# WSTL18P2_SHIELD.net
KiCad netlist of a schematic drawn in EAGLE
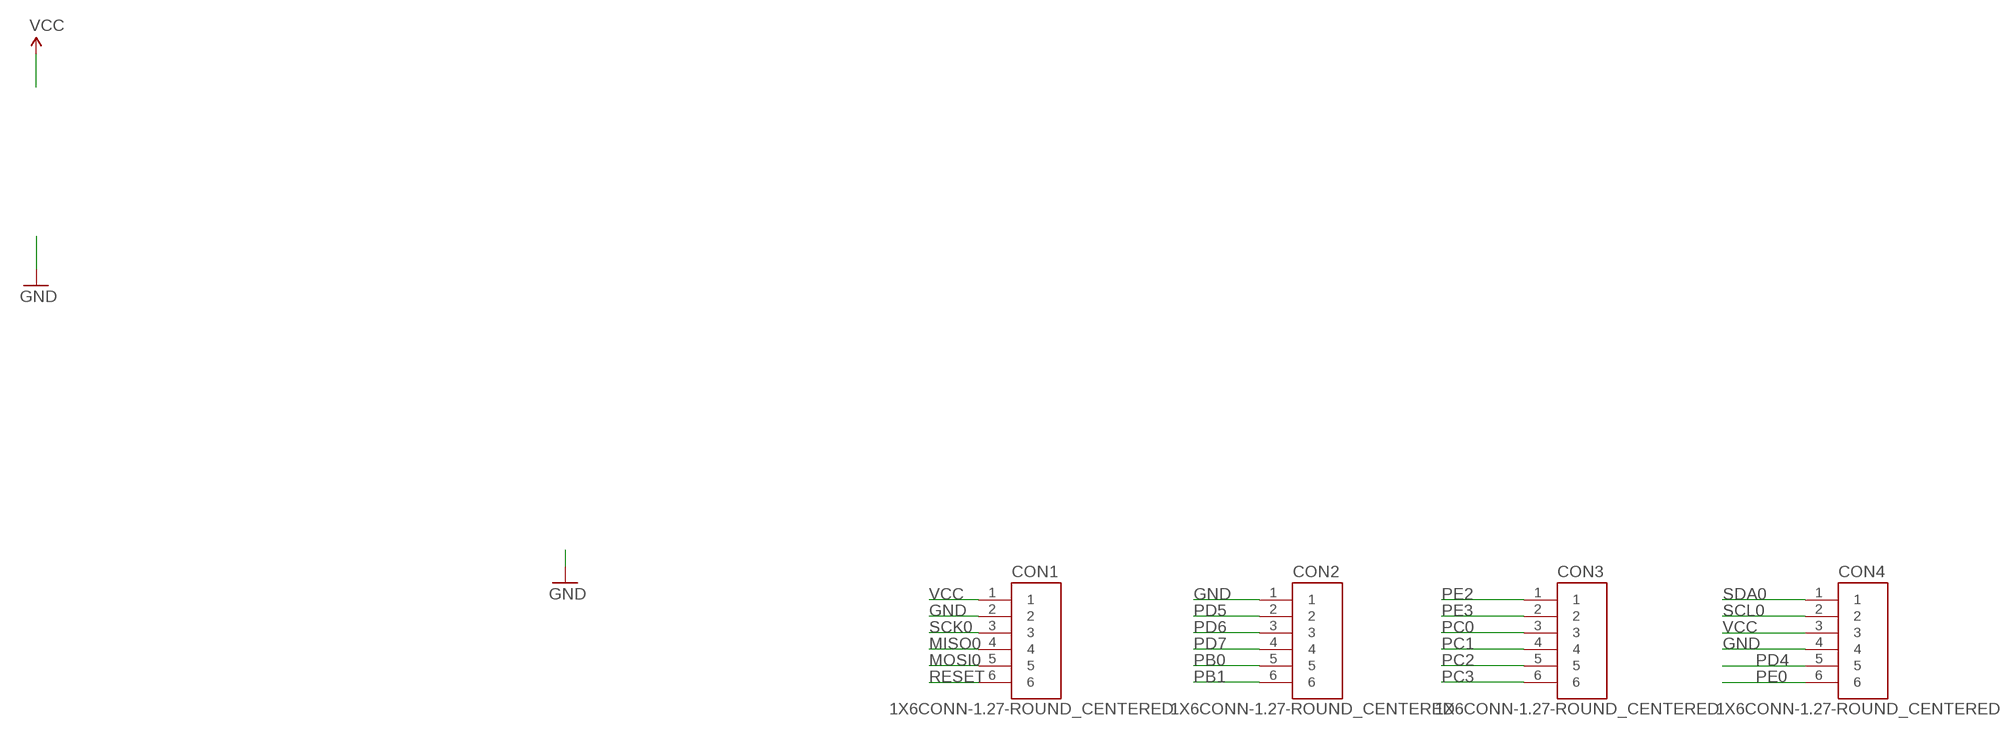
[diagram p0: schematic, sheet 1]

(export (version "E")
  (design (tool "Eeschema 10.0.6"))
  (components
    (comp (ref "CON1")
      (value "1X6CONN-1.27-ROUND_CENTERED")
      (footprint "eagle-import:1X6_1.27_ROUND_CENTERED")
      (libsource (lib "eagle-import") (part "1X6CONN-1.27-ROUND_CENTERED"))
    )
    (comp (ref "CON2")
      (value "1X6CONN-1.27-ROUND_CENTERED")
      (footprint "eagle-import:1X6_1.27_ROUND_CENTERED")
      (libsource (lib "eagle-import") (part "1X6CONN-1.27-ROUND_CENTERED"))
    )
    (comp (ref "CON3")
      (value "1X6CONN-1.27-ROUND_CENTERED")
      (footprint "eagle-import:1X6_1.27_ROUND_CENTERED")
      (libsource (lib "eagle-import") (part "1X6CONN-1.27-ROUND_CENTERED"))
    )
    (comp (ref "CON4")
      (value "1X6CONN-1.27-ROUND_CENTERED")
      (footprint "eagle-import:1X6_1.27_ROUND_CENTERED")
      (libsource (lib "eagle-import") (part "1X6CONN-1.27-ROUND_CENTERED"))
    )
  )
  (nets
    (net (code "1") (name "/MISO0") (class "Default")
      (node (ref "CON1") (pin "4") (pinfunction "4_4") (pintype "bidirectional"))
    )
    (net (code "2") (name "/MOSI0") (class "Default")
      (node (ref "CON1") (pin "5") (pinfunction "5_5") (pintype "bidirectional"))
    )
    (net (code "3") (name "/PB0") (class "Default")
      (node (ref "CON2") (pin "5") (pinfunction "5_5") (pintype "bidirectional"))
    )
    (net (code "4") (name "/PB1") (class "Default")
      (node (ref "CON2") (pin "6") (pinfunction "6_6") (pintype "bidirectional"))
    )
    (net (code "5") (name "/PC0") (class "Default")
      (node (ref "CON3") (pin "3") (pinfunction "3_3") (pintype "bidirectional"))
    )
    (net (code "6") (name "/PC1") (class "Default")
      (node (ref "CON3") (pin "4") (pinfunction "4_4") (pintype "bidirectional"))
    )
    (net (code "7") (name "/PC2") (class "Default")
      (node (ref "CON3") (pin "5") (pinfunction "5_5") (pintype "bidirectional"))
    )
    (net (code "8") (name "/PC3") (class "Default")
      (node (ref "CON3") (pin "6") (pinfunction "6_6") (pintype "bidirectional"))
    )
    (net (code "9") (name "/PD4") (class "Default")
      (node (ref "CON4") (pin "5") (pinfunction "5_5") (pintype "bidirectional"))
    )
    (net (code "10") (name "/PD5") (class "Default")
      (node (ref "CON2") (pin "2") (pinfunction "2_2") (pintype "bidirectional"))
    )
    (net (code "11") (name "/PD6") (class "Default")
      (node (ref "CON2") (pin "3") (pinfunction "3_3") (pintype "bidirectional"))
    )
    (net (code "12") (name "/PD7") (class "Default")
      (node (ref "CON2") (pin "4") (pinfunction "4_4") (pintype "bidirectional"))
    )
    (net (code "13") (name "/PE0") (class "Default")
      (node (ref "CON4") (pin "6") (pinfunction "6_6") (pintype "bidirectional"))
    )
    (net (code "14") (name "/PE2") (class "Default")
      (node (ref "CON3") (pin "1") (pinfunction "1_1") (pintype "bidirectional"))
    )
    (net (code "15") (name "/PE3") (class "Default")
      (node (ref "CON3") (pin "2") (pinfunction "2_2") (pintype "bidirectional"))
    )
    (net (code "16") (name "/RESET") (class "Default")
      (node (ref "CON1") (pin "6") (pinfunction "6_6") (pintype "bidirectional"))
    )
    (net (code "17") (name "/SCK0") (class "Default")
      (node (ref "CON1") (pin "3") (pinfunction "3_3") (pintype "bidirectional"))
    )
    (net (code "18") (name "/SCL0") (class "Default")
      (node (ref "CON4") (pin "2") (pinfunction "2_2") (pintype "bidirectional"))
    )
    (net (code "19") (name "/SDA0") (class "Default")
      (node (ref "CON4") (pin "1") (pinfunction "1_1") (pintype "bidirectional"))
    )
    (net (code "20") (name "GND") (class "Default")
      (node (ref "CON1") (pin "2") (pinfunction "2_2") (pintype "bidirectional"))
      (node (ref "CON2") (pin "1") (pinfunction "1_1") (pintype "bidirectional"))
      (node (ref "CON4") (pin "4") (pinfunction "4_4") (pintype "bidirectional"))
    )
    (net (code "21") (name "VCC") (class "Default")
      (node (ref "CON1") (pin "1") (pinfunction "1_1") (pintype "bidirectional"))
      (node (ref "CON4") (pin "3") (pinfunction "3_3") (pintype "bidirectional"))
    )
  )
)
